# power_supply_v2.net
KiCad netlist of a schematic drawn in Altium Designer
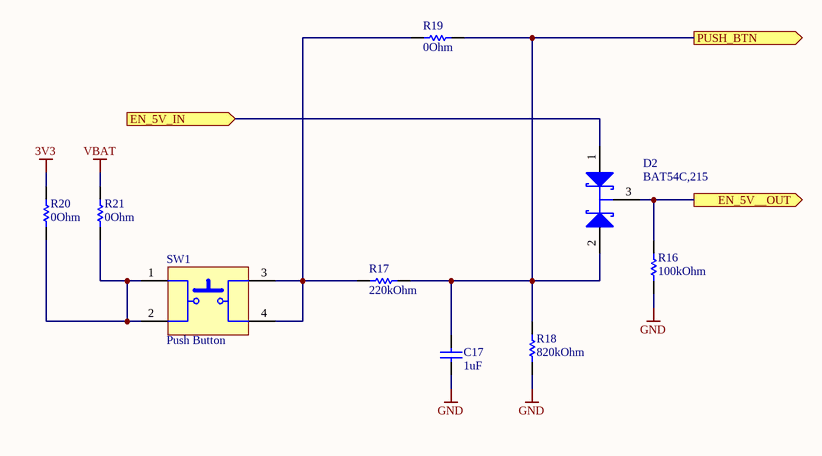
[diagram p0: power_supply_v2.SchDoc]

(export (version "E")
  (design (tool "Eeschema 10.0.6"))
  (components
    (comp (ref "C17")
      (value "1uF")
      (footprint "CAP_0804")
      (fields
        (field (name "TOLERANCE") "10%")
        (field (name "PARTNUMBER") "1206GC102KAT1A")
        (field (name "MANUFACTURER") "AVX")
      )
      (libsource (lib "Schlib") (part "CAP_1UF"))
    )
    (comp (ref "D2")
      (value "BAT54C,215")
      (footprint "SOT23")
      (description "Schottky Barrier Diode, 30 V, 3-Pin SOT23, RoHS, Tape and Reel")
      (fields (field (name "MANUFACTURER") "NXP Semiconductors"))
      (libsource (lib "Schlib") (part "DIODE_BAT54C"))
    )
    (comp (ref "R16")
      (value "100kOhm")
      (footprint "RES_0804")
      (fields (field (name "PART NUMBER") "CRCW120647K0FKEA") (field (name "MANUFACTURER") "Vishay Dale"))
      (libsource (lib "Schlib") (part "RES_100K"))
    )
    (comp (ref "R17")
      (value "220kOhm")
      (footprint "RES_0804")
      (fields (field (name "PART NUMBER") "CRCW120647K0FKEA") (field (name "MANUFACTURER") "Vishay Dale"))
      (libsource (lib "Schlib") (part "RES_220K"))
    )
    (comp (ref "R18")
      (value "820kOhm")
      (footprint "RES_0804")
      (fields (field (name "PART NUMBER") "CRCW120647K0FKEA") (field (name "MANUFACTURER") "Vishay Dale"))
      (libsource (lib "Schlib") (part "RES_820K"))
    )
    (comp (ref "R19")
      (value "0Ohm")
      (footprint "RES_0804")
      (fields (field (name "PART NUMBER") "CRCW120647K0FKEA") (field (name "MANUFACTURER") "Vishay Dale"))
      (libsource (lib "Schlib") (part "RES_0R"))
    )
    (comp (ref "R20")
      (value "0Ohm")
      (footprint "RES_0804")
      (fields (field (name "PART NUMBER") "CRCW120647K0FKEA") (field (name "MANUFACTURER") "Vishay Dale"))
      (libsource (lib "Schlib") (part "RES_0R"))
    )
    (comp (ref "R21")
      (value "0Ohm")
      (footprint "RES_0804")
      (fields (field (name "PART NUMBER") "CRCW120647K0FKEA") (field (name "MANUFACTURER") "Vishay Dale"))
      (libsource (lib "Schlib") (part "RES_0R"))
    )
    (comp (ref "SW1")
      (value "Push Button")
      (footprint "SWITCH")
      (description "Micro Miniature Push Button Switch FSM JSM, 50 mA, -35 to 85 degC, 4-Pin SMD, RoHS, Tape and Reel")
      (fields (field (name "MANUFACTURER") "TE Connectivity"))
      (libsource (lib "Schlib") (part "SWITCH"))
    )
  )
  (nets
    (net (code "1") (name "/EN_5V_IN") (class "Default")
      (node (ref "D2") (pin "1") (pinfunction "A_1") (pintype "passive"))
    )
    (net (code "2") (name "/EN_5V__OUT") (class "Default")
      (node (ref "D2") (pin "3") (pinfunction "K_3") (pintype "passive"))
      (node (ref "R16") (pin "2") (pinfunction "2_2") (pintype "passive"))
    )
    (net (code "3") (name "/PUSH_BTN") (class "Default")
      (node (ref "C17") (pin "2") (pinfunction "2_2") (pintype "passive"))
      (node (ref "D2") (pin "2") (pinfunction "A_2") (pintype "passive"))
      (node (ref "R17") (pin "2") (pinfunction "2_2") (pintype "passive"))
      (node (ref "R18") (pin "2") (pinfunction "2_2") (pintype "passive"))
      (node (ref "R19") (pin "2") (pinfunction "2_2") (pintype "passive"))
    )
    (net (code "4") (name "3V3") (class "Default")
      (node (ref "R20") (pin "2") (pinfunction "2_2") (pintype "passive"))
    )
    (net (code "5") (name "GND") (class "Default")
      (node (ref "C17") (pin "1") (pinfunction "1_1") (pintype "passive"))
      (node (ref "R16") (pin "1") (pinfunction "1_1") (pintype "passive"))
      (node (ref "R18") (pin "1") (pinfunction "1_1") (pintype "passive"))
    )
    (net (code "6") (name "Net-(R17-Pad1)") (class "Default")
      (node (ref "R17") (pin "1") (pinfunction "1_1") (pintype "passive"))
      (node (ref "R19") (pin "1") (pinfunction "1_1") (pintype "passive"))
      (node (ref "SW1") (pin "3") (pinfunction "3_3") (pintype "passive"))
      (node (ref "SW1") (pin "4") (pinfunction "4_4") (pintype "passive"))
    )
    (net (code "7") (name "Net-(R20-Pad1)") (class "Default")
      (node (ref "R20") (pin "1") (pinfunction "1_1") (pintype "passive"))
      (node (ref "R21") (pin "1") (pinfunction "1_1") (pintype "passive"))
      (node (ref "SW1") (pin "1") (pinfunction "1_1") (pintype "passive"))
      (node (ref "SW1") (pin "2") (pinfunction "2_2") (pintype "passive"))
    )
    (net (code "8") (name "VBAT") (class "Default")
      (node (ref "R21") (pin "2") (pinfunction "2_2") (pintype "passive"))
    )
  )
)
